# Automatic_Battery_Charger.net
KiCad netlist of a schematic drawn in EAGLE
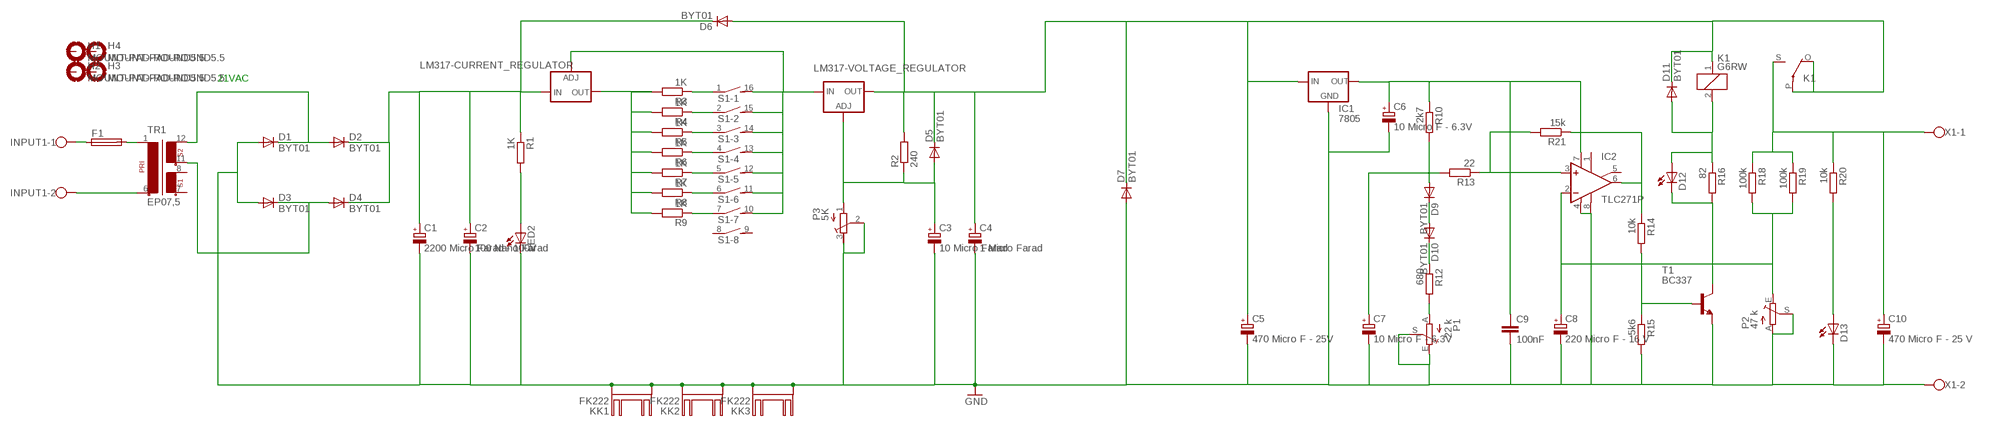
[diagram p0: schematic, sheet 1]

(export (version "E")
  (design (tool "Eeschema 10.0.6"))
  (components
    (comp (ref "C1")
      (value "2200 Micro Farad - 100V")
      (footprint "eagle-import:EB35D")
      (libsource (lib "eagle-import") (part "CPOL-EUE10-35"))
    )
    (comp (ref "C2")
      (value "100 Nano Farad")
      (footprint "eagle-import:E1,8-4")
      (libsource (lib "eagle-import") (part "CPOL-EUE1.8-4"))
    )
    (comp (ref "C3")
      (value "10 Micro Farad")
      (footprint "eagle-import:E2-5")
      (libsource (lib "eagle-import") (part "CPOL-EUE2-5"))
    )
    (comp (ref "C4")
      (value "1 Micro Farad")
      (footprint "eagle-import:E2-5")
      (libsource (lib "eagle-import") (part "CPOL-EUE2-5"))
    )
    (comp (ref "C5")
      (value "470 Micro F - 25V")
      (footprint "eagle-import:E3,5-10")
      (libsource (lib "eagle-import") (part "CPOL-EUE3.5-10"))
    )
    (comp (ref "C6")
      (value "10 Micro F - 6.3V")
      (footprint "eagle-import:E2-5")
      (libsource (lib "eagle-import") (part "CPOL-EUE2-5"))
    )
    (comp (ref "C7")
      (value "10 Micro F - 6.3V")
      (footprint "eagle-import:E2-5")
      (libsource (lib "eagle-import") (part "CPOL-EUE2-5"))
    )
    (comp (ref "C8")
      (value "220 Micro F - 16 V")
      (footprint "eagle-import:E2,5-7")
      (libsource (lib "eagle-import") (part "CPOL-EUE2.5-7"))
    )
    (comp (ref "C9")
      (value "100nF")
      (footprint "eagle-import:C025-030X050")
      (libsource (lib "eagle-import") (part "C-EU025-030X050"))
    )
    (comp (ref "C10")
      (value "470 Micro F - 25 V")
      (footprint "eagle-import:E3,5-10")
      (libsource (lib "eagle-import") (part "CPOL-EUE3.5-10"))
    )
    (comp (ref "D1")
      (value "BYT01")
      (footprint "eagle-import:F126-10")
      (libsource (lib "eagle-import") (part "BYT01"))
    )
    (comp (ref "D2")
      (value "BYT01")
      (footprint "eagle-import:F126-10")
      (libsource (lib "eagle-import") (part "BYT01"))
    )
    (comp (ref "D3")
      (value "BYT01")
      (footprint "eagle-import:F126-10")
      (libsource (lib "eagle-import") (part "BYT01"))
    )
    (comp (ref "D4")
      (value "BYT01")
      (footprint "eagle-import:F126-10")
      (libsource (lib "eagle-import") (part "BYT01"))
    )
    (comp (ref "D5")
      (value "BYT01")
      (footprint "eagle-import:F126-10")
      (libsource (lib "eagle-import") (part "BYT01"))
    )
    (comp (ref "D6")
      (value "BYT01")
      (footprint "eagle-import:F126-10")
      (libsource (lib "eagle-import") (part "BYT01"))
    )
    (comp (ref "D7")
      (value "BYT01")
      (footprint "eagle-import:F126-10")
      (libsource (lib "eagle-import") (part "BYT01"))
    )
    (comp (ref "D9")
      (value "BYT01")
      (footprint "eagle-import:F126-10")
      (libsource (lib "eagle-import") (part "BYT01"))
    )
    (comp (ref "D10")
      (value "BYT01")
      (footprint "eagle-import:F126-10")
      (libsource (lib "eagle-import") (part "BYT01"))
    )
    (comp (ref "D11")
      (value "BYT01")
      (footprint "eagle-import:F126-10")
      (libsource (lib "eagle-import") (part "BYT01"))
    )
    (comp (ref "D12")
      (value "LED5MM")
      (footprint "eagle-import:LED5MM")
      (libsource (lib "eagle-import") (part "LED5MM"))
    )
    (comp (ref "D13")
      (value "LED5MM")
      (footprint "eagle-import:LED5MM")
      (libsource (lib "eagle-import") (part "LED5MM"))
    )
    (comp (ref "F1")
      (value "SH22,5A")
      (footprint "eagle-import:SH22,5A")
      (fields (field (name "MPN") "0031.7701.11"))
      (libsource (lib "eagle-import") (part "SH22,5A"))
    )
    (comp (ref "H1")
      (value "MOUNT-PAD-ROUND5.5")
      (footprint "eagle-import:5,5-PAD")
      (libsource (lib "eagle-import") (part "MOUNT-PAD-ROUND5.5"))
    )
    (comp (ref "H2")
      (value "MOUNT-PAD-ROUND5.5")
      (footprint "eagle-import:5,5-PAD")
      (libsource (lib "eagle-import") (part "MOUNT-PAD-ROUND5.5"))
    )
    (comp (ref "H3")
      (value "MOUNT-PAD-ROUND5.5")
      (footprint "eagle-import:5,5-PAD")
      (libsource (lib "eagle-import") (part "MOUNT-PAD-ROUND5.5"))
    )
    (comp (ref "H4")
      (value "MOUNT-PAD-ROUND5.5")
      (footprint "eagle-import:5,5-PAD")
      (libsource (lib "eagle-import") (part "MOUNT-PAD-ROUND5.5"))
    )
    (comp (ref "IC1")
      (value "7805")
      (footprint "eagle-import:78XXS")
      (libsource (lib "eagle-import") (part "78XXS"))
    )
    (comp (ref "IC2")
      (value "TLC271P")
      (footprint "eagle-import:DIL08")
      (libsource (lib "eagle-import") (part "TLC271P"))
    )
    (comp (ref "INPUT1")
      (value "W237-102")
      (footprint "eagle-import:W237-102")
      (fields (field (name "MPN") "237-102"))
      (libsource (lib "eagle-import") (part "W237-102"))
    )
    (comp (ref "K1")
      (value "G6RW")
      (footprint "eagle-import:G6RW")
      (libsource (lib "eagle-import") (part "G6RW"))
    )
    (comp (ref "KK1")
      (value "FK222")
      (footprint "eagle-import:FK222")
      (libsource (lib "eagle-import") (part "FK222"))
    )
    (comp (ref "KK2")
      (value "FK222")
      (footprint "eagle-import:FK222")
      (libsource (lib "eagle-import") (part "FK222"))
    )
    (comp (ref "KK3")
      (value "FK222")
      (footprint "eagle-import:FK222")
      (libsource (lib "eagle-import") (part "FK222"))
    )
    (comp (ref "LED2")
      (value "LED5MM")
      (footprint "eagle-import:LED5MM")
      (libsource (lib "eagle-import") (part "LED5MM"))
    )
    (comp (ref "LM317-CURRENT_REGULATOR")
      (value "LM138-TS")
      (footprint "eagle-import:TO220S")
      (libsource (lib "eagle-import") (part "LM138-TS"))
    )
    (comp (ref "LM317-VOLTAGE_REGULATOR")
      (value "LM138-TS")
      (footprint "eagle-import:TO220S")
      (libsource (lib "eagle-import") (part "LM138-TS"))
    )
    (comp (ref "P1")
      (value "22 k")
      (footprint "eagle-import:LI10")
      (libsource (lib "eagle-import") (part "TRIM_EU-LI10"))
    )
    (comp (ref "P2")
      (value "47 k")
      (footprint "eagle-import:LI10")
      (libsource (lib "eagle-import") (part "TRIM_EU-LI10"))
    )
    (comp (ref "P3")
      (value "5K")
      (footprint "eagle-import:RTRIM64X")
      (libsource (lib "eagle-import") (part "R-TRIMM64X"))
    )
    (comp (ref "R1")
      (value "1K")
      (footprint "eagle-import:0207_7")
      (libsource (lib "eagle-import") (part "R-EU_0207/7"))
    )
    (comp (ref "R2")
      (value "240")
      (footprint "eagle-import:0207_7")
      (libsource (lib "eagle-import") (part "R-EU_0207/7"))
    )
    (comp (ref "R3")
      (value "1K")
      (footprint "eagle-import:0207_7")
      (libsource (lib "eagle-import") (part "R-EU_0207/7"))
    )
    (comp (ref "R4")
      (value "1K")
      (footprint "eagle-import:0207_7")
      (libsource (lib "eagle-import") (part "R-EU_0207/7"))
    )
    (comp (ref "R5")
      (value "1K")
      (footprint "eagle-import:0207_7")
      (libsource (lib "eagle-import") (part "R-EU_0207/7"))
    )
    (comp (ref "R6")
      (value "1K")
      (footprint "eagle-import:0207_10")
      (libsource (lib "eagle-import") (part "R-EU_0207/10"))
    )
    (comp (ref "R7")
      (value "1K")
      (footprint "eagle-import:0207_10")
      (libsource (lib "eagle-import") (part "R-EU_0207/10"))
    )
    (comp (ref "R8")
      (value "1K")
      (footprint "eagle-import:0207_15")
      (libsource (lib "eagle-import") (part "R-EU_0207/15"))
    )
    (comp (ref "R9")
      (value "1K")
      (footprint "eagle-import:0207_15")
      (libsource (lib "eagle-import") (part "R-EU_0207/15"))
    )
    (comp (ref "R10")
      (value "2k7")
      (footprint "eagle-import:0207_7")
      (libsource (lib "eagle-import") (part "R-EU_0207/7"))
    )
    (comp (ref "R12")
      (value "680")
      (footprint "eagle-import:0207_7")
      (libsource (lib "eagle-import") (part "R-EU_0207/7"))
    )
    (comp (ref "R13")
      (value "22")
      (footprint "eagle-import:0207_7")
      (libsource (lib "eagle-import") (part "R-EU_0207/7"))
    )
    (comp (ref "R14")
      (value "10k")
      (footprint "eagle-import:0207_7")
      (libsource (lib "eagle-import") (part "R-EU_0207/7"))
    )
    (comp (ref "R15")
      (value "5k6")
      (footprint "eagle-import:0207_7")
      (libsource (lib "eagle-import") (part "R-EU_0207/7"))
    )
    (comp (ref "R16")
      (value "82")
      (footprint "eagle-import:0207_7")
      (libsource (lib "eagle-import") (part "R-EU_0207/7"))
    )
    (comp (ref "R18")
      (value "100k")
      (footprint "eagle-import:0207_7")
      (libsource (lib "eagle-import") (part "R-EU_0207/7"))
    )
    (comp (ref "R19")
      (value "100k")
      (footprint "eagle-import:0207_7")
      (libsource (lib "eagle-import") (part "R-EU_0207/7"))
    )
    (comp (ref "R20")
      (value "10k")
      (footprint "eagle-import:0207_7")
      (libsource (lib "eagle-import") (part "R-EU_0207/7"))
    )
    (comp (ref "R21")
      (value "15k")
      (footprint "eagle-import:0207_7")
      (libsource (lib "eagle-import") (part "R-EU_0207/7"))
    )
    (comp (ref "S1")
      (value "DIP08SB")
      (footprint "eagle-import:DIP08SB")
      (libsource (lib "eagle-import") (part "DIP08SB"))
    )
    (comp (ref "T1")
      (value "BC337")
      (footprint "eagle-import:TO92")
      (libsource (lib "eagle-import") (part "BC337"))
    )
    (comp (ref "TR1")
      (value "EP07,5")
      (footprint "eagle-import:EP07,5")
      (libsource (lib "eagle-import") (part "EP07,5"))
    )
    (comp (ref "X1")
      (value "W237-102")
      (footprint "eagle-import:W237-102")
      (fields (field (name "MPN") "237-102"))
      (libsource (lib "eagle-import") (part "W237-102"))
    )
  )
  (nets
    (net (code "1") (name "GND") (class "Default")
      (node (ref "C1") (pin "-") (pinfunction "-_-") (pintype "passive"))
      (node (ref "C10") (pin "-") (pinfunction "-_-") (pintype "passive"))
      (node (ref "C2") (pin "-") (pinfunction "-_-") (pintype "passive"))
      (node (ref "C3") (pin "-") (pinfunction "-_-") (pintype "passive"))
      (node (ref "C4") (pin "-") (pinfunction "-_-") (pintype "passive"))
      (node (ref "C5") (pin "-") (pinfunction "-_-") (pintype "passive"))
      (node (ref "C6") (pin "-") (pinfunction "-_-") (pintype "passive"))
      (node (ref "C7") (pin "-") (pinfunction "-_-") (pintype "passive"))
      (node (ref "C8") (pin "-") (pinfunction "-_-") (pintype "passive"))
      (node (ref "C9") (pin "2") (pinfunction "2_2") (pintype "passive"))
      (node (ref "D1") (pin "A") (pinfunction "A_A") (pintype "passive"))
      (node (ref "D13") (pin "K") (pinfunction "C_K") (pintype "passive"))
      (node (ref "D3") (pin "A") (pinfunction "A_A") (pintype "passive"))
      (node (ref "D7") (pin "A") (pinfunction "A_A") (pintype "passive"))
      (node (ref "IC1") (pin "GND") (pinfunction "GND_GND") (pintype "input"))
      (node (ref "IC2") (pin "4") (pinfunction "V-_4") (pintype "power_in"))
      (node (ref "IC2") (pin "8") (pinfunction "OPT_8") (pintype "passive"))
      (node (ref "KK1") (pin "A2,8") (pinfunction "K_A2,8") (pintype "passive"))
      (node (ref "KK1") (pin "B2,8") (pinfunction "K_B2,8") (pintype "passive"))
      (node (ref "KK2") (pin "A2,8") (pinfunction "K_A2,8") (pintype "passive"))
      (node (ref "KK2") (pin "B2,8") (pinfunction "K_B2,8") (pintype "passive"))
      (node (ref "KK3") (pin "A2,8") (pinfunction "K_A2,8") (pintype "passive"))
      (node (ref "KK3") (pin "B2,8") (pinfunction "K_B2,8") (pintype "passive"))
      (node (ref "LED2") (pin "K") (pinfunction "C_K") (pintype "passive"))
      (node (ref "P1") (pin "E") (pinfunction "E_E") (pintype "passive"))
      (node (ref "P1") (pin "S") (pinfunction "S_S") (pintype "passive"))
      (node (ref "P2") (pin "A") (pinfunction "A_A") (pintype "passive"))
      (node (ref "P2") (pin "S") (pinfunction "S_S") (pintype "passive"))
      (node (ref "P3") (pin "2") (pinfunction "S_2") (pintype "passive"))
      (node (ref "P3") (pin "3") (pinfunction "A_3") (pintype "passive"))
      (node (ref "R15") (pin "2") (pinfunction "2_2") (pintype "passive"))
      (node (ref "T1") (pin "1") (pinfunction "E_1") (pintype "passive"))
      (node (ref "X1") (pin "2") (pinfunction "KL_2") (pintype "passive"))
    )
    (net (code "2") (name "Net-(C7-Pad+)") (class "Default")
      (node (ref "C7") (pin "+") (pinfunction "+_+") (pintype "passive"))
      (node (ref "D9") (pin "A") (pinfunction "A_A") (pintype "passive"))
      (node (ref "R10") (pin "2") (pinfunction "2_2") (pintype "passive"))
      (node (ref "R13") (pin "2") (pinfunction "2_2") (pintype "passive"))
    )
    (net (code "3") (name "Net-(D10-PadA)") (class "Default")
      (node (ref "D10") (pin "A") (pinfunction "A_A") (pintype "passive"))
      (node (ref "D9") (pin "C") (pinfunction "C_C") (pintype "passive"))
    )
    (net (code "4") (name "Net-(D10-PadC)") (class "Default")
      (node (ref "D10") (pin "C") (pinfunction "C_C") (pintype "passive"))
      (node (ref "R12") (pin "1") (pinfunction "1_1") (pintype "passive"))
    )
    (net (code "5") (name "Net-(D11-PadA)") (class "Default")
      (node (ref "D11") (pin "A") (pinfunction "A_A") (pintype "passive"))
      (node (ref "D12") (pin "A") (pinfunction "A_A") (pintype "passive"))
      (node (ref "K1") (pin "2") (pinfunction "2_2") (pintype "passive"))
      (node (ref "R16") (pin "1") (pinfunction "1_1") (pintype "passive"))
    )
    (net (code "6") (name "Net-(D12-C)") (class "Default")
      (node (ref "D12") (pin "K") (pinfunction "C_K") (pintype "passive"))
      (node (ref "R16") (pin "2") (pinfunction "2_2") (pintype "passive"))
      (node (ref "T1") (pin "3") (pinfunction "C_3") (pintype "passive"))
    )
    (net (code "7") (name "Net-(D13-PadA)") (class "Default")
      (node (ref "D13") (pin "A") (pinfunction "A_A") (pintype "passive"))
      (node (ref "R20") (pin "2") (pinfunction "2_2") (pintype "passive"))
    )
    (net (code "8") (name "Net-(F1-Pad2)") (class "Default")
      (node (ref "F1") (pin "2") (pinfunction "2_2") (pintype "passive"))
      (node (ref "TR1") (pin "1") (pinfunction "1_1") (pintype "passive"))
    )
    (net (code "9") (name "Net-(IC2-+IN)") (class "Default")
      (node (ref "IC2") (pin "3") (pinfunction "+IN_3") (pintype "input"))
      (node (ref "R13") (pin "1") (pinfunction "1_1") (pintype "passive"))
      (node (ref "R21") (pin "2") (pinfunction "2_2") (pintype "passive"))
    )
    (net (code "10") (name "Net-(IC2--IN)") (class "Default")
      (node (ref "C8") (pin "+") (pinfunction "+_+") (pintype "passive"))
      (node (ref "IC2") (pin "2") (pinfunction "-IN_2") (pintype "input"))
      (node (ref "P2") (pin "E") (pinfunction "E_E") (pintype "passive"))
      (node (ref "R18") (pin "2") (pinfunction "2_2") (pintype "passive"))
      (node (ref "R19") (pin "2") (pinfunction "2_2") (pintype "passive"))
    )
    (net (code "11") (name "Net-(IC2-OUT)") (class "Default")
      (node (ref "IC2") (pin "6") (pinfunction "OUT_6") (pintype "output"))
      (node (ref "R14") (pin "1") (pinfunction "1_1") (pintype "passive"))
      (node (ref "R21") (pin "1") (pinfunction "1_1") (pintype "passive"))
    )
    (net (code "12") (name "Net-(IC2-V+)") (class "Default")
      (node (ref "C6") (pin "+") (pinfunction "+_+") (pintype "passive"))
      (node (ref "C9") (pin "1") (pinfunction "1_1") (pintype "passive"))
      (node (ref "IC1") (pin "OUT") (pinfunction "OUT_OUT") (pintype "passive"))
      (node (ref "IC2") (pin "7") (pinfunction "V+_7") (pintype "power_in"))
      (node (ref "R10") (pin "1") (pinfunction "1_1") (pintype "passive"))
    )
    (net (code "13") (name "Net-(INPUT1A-KL)") (class "Default")
      (node (ref "F1") (pin "1") (pinfunction "1_1") (pintype "passive"))
      (node (ref "INPUT1") (pin "1") (pinfunction "KL_1") (pintype "passive"))
    )
    (net (code "14") (name "Net-(INPUT1B-KL)") (class "Default")
      (node (ref "INPUT1") (pin "2") (pinfunction "KL_2") (pintype "passive"))
      (node (ref "TR1") (pin "6") (pinfunction "2_6") (pintype "passive"))
    )
    (net (code "15") (name "Net-(LED2-PadA)") (class "Default")
      (node (ref "LED2") (pin "A") (pinfunction "A_A") (pintype "passive"))
      (node (ref "R1") (pin "2") (pinfunction "2_2") (pintype "passive"))
    )
    (net (code "16") (name "Net-(LM317-CURRENT_REGULATOR-ADJ)") (class "Default")
      (node (ref "LM317-CURRENT_REGULATOR") (pin "1") (pinfunction "ADJ_1") (pintype "input"))
      (node (ref "LM317-VOLTAGE_REGULATOR") (pin "3") (pinfunction "IN_3") (pintype "input"))
      (node (ref "S1") (pin "10") (pinfunction "2_10") (pintype "passive"))
      (node (ref "S1") (pin "11") (pinfunction "2_11") (pintype "passive"))
      (node (ref "S1") (pin "12") (pinfunction "2_12") (pintype "passive"))
      (node (ref "S1") (pin "13") (pinfunction "2_13") (pintype "passive"))
      (node (ref "S1") (pin "14") (pinfunction "2_14") (pintype "passive"))
      (node (ref "S1") (pin "15") (pinfunction "2_15") (pintype "passive"))
      (node (ref "S1") (pin "16") (pinfunction "2_16") (pintype "passive"))
    )
    (net (code "17") (name "Net-(LM317-CURRENT_REGULATOR-IN)") (class "Default")
      (node (ref "C1") (pin "+") (pinfunction "+_+") (pintype "passive"))
      (node (ref "C2") (pin "+") (pinfunction "+_+") (pintype "passive"))
      (node (ref "D2") (pin "C") (pinfunction "C_C") (pintype "passive"))
      (node (ref "D4") (pin "C") (pinfunction "C_C") (pintype "passive"))
      (node (ref "D6") (pin "C") (pinfunction "C_C") (pintype "passive"))
      (node (ref "LM317-CURRENT_REGULATOR") (pin "3") (pinfunction "IN_3") (pintype "input"))
      (node (ref "R1") (pin "1") (pinfunction "1_1") (pintype "passive"))
    )
    (net (code "18") (name "Net-(LM317-CURRENT_REGULATOR-OUT)") (class "Default")
      (node (ref "LM317-CURRENT_REGULATOR") (pin "2") (pinfunction "OUT_2") (pintype "passive"))
      (node (ref "R3") (pin "2") (pinfunction "2_2") (pintype "passive"))
      (node (ref "R4") (pin "2") (pinfunction "2_2") (pintype "passive"))
      (node (ref "R5") (pin "2") (pinfunction "2_2") (pintype "passive"))
      (node (ref "R6") (pin "2") (pinfunction "2_2") (pintype "passive"))
      (node (ref "R7") (pin "2") (pinfunction "2_2") (pintype "passive"))
      (node (ref "R8") (pin "2") (pinfunction "2_2") (pintype "passive"))
      (node (ref "R9") (pin "2") (pinfunction "2_2") (pintype "passive"))
    )
    (net (code "19") (name "Net-(LM317-VOLTAGE_REGULATOR-ADJ)") (class "Default")
      (node (ref "C3") (pin "+") (pinfunction "+_+") (pintype "passive"))
      (node (ref "D5") (pin "A") (pinfunction "A_A") (pintype "passive"))
      (node (ref "LM317-VOLTAGE_REGULATOR") (pin "1") (pinfunction "ADJ_1") (pintype "input"))
      (node (ref "P3") (pin "1") (pinfunction "E_1") (pintype "passive"))
      (node (ref "R2") (pin "1") (pinfunction "1_1") (pintype "passive"))
    )
    (net (code "20") (name "Net-(LM317-VOLTAGE_REGULATOR-OUT)") (class "Default")
      (node (ref "C4") (pin "+") (pinfunction "+_+") (pintype "passive"))
      (node (ref "C5") (pin "+") (pinfunction "+_+") (pintype "passive"))
      (node (ref "D11") (pin "C") (pinfunction "C_C") (pintype "passive"))
      (node (ref "D5") (pin "C") (pinfunction "C_C") (pintype "passive"))
      (node (ref "D6") (pin "A") (pinfunction "A_A") (pintype "passive"))
      (node (ref "D7") (pin "C") (pinfunction "C_C") (pintype "passive"))
      (node (ref "IC1") (pin "IN") (pinfunction "IN_IN") (pintype "input"))
      (node (ref "K1") (pin "1") (pinfunction "1_1") (pintype "passive"))
      (node (ref "K1") (pin "O") (pinfunction "O_O") (pintype "passive"))
      (node (ref "K1") (pin "P") (pinfunction "P_P") (pintype "passive"))
      (node (ref "LM317-VOLTAGE_REGULATOR") (pin "2") (pinfunction "OUT_2") (pintype "passive"))
      (node (ref "R2") (pin "2") (pinfunction "2_2") (pintype "passive"))
    )
    (net (code "21") (name "Net-(P1-PadA)") (class "Default")
      (node (ref "P1") (pin "A") (pinfunction "A_A") (pintype "passive"))
      (node (ref "R12") (pin "2") (pinfunction "2_2") (pintype "passive"))
    )
    (net (code "22") (name "Net-(R3-Pad1)") (class "Default")
      (node (ref "R3") (pin "1") (pinfunction "1_1") (pintype "passive"))
      (node (ref "S1") (pin "1") (pinfunction "1_1") (pintype "passive"))
    )
    (net (code "23") (name "Net-(S1B-1)") (class "Default")
      (node (ref "R4") (pin "1") (pinfunction "1_1") (pintype "passive"))
      (node (ref "S1") (pin "2") (pinfunction "1_2") (pintype "passive"))
    )
    (net (code "24") (name "Net-(S1C-1)") (class "Default")
      (node (ref "R5") (pin "1") (pinfunction "1_1") (pintype "passive"))
      (node (ref "S1") (pin "3") (pinfunction "1_3") (pintype "passive"))
    )
    (net (code "25") (name "Net-(S1D-1)") (class "Default")
      (node (ref "R6") (pin "1") (pinfunction "1_1") (pintype "passive"))
      (node (ref "S1") (pin "4") (pinfunction "1_4") (pintype "passive"))
    )
    (net (code "26") (name "Net-(S1E-1)") (class "Default")
      (node (ref "R7") (pin "1") (pinfunction "1_1") (pintype "passive"))
      (node (ref "S1") (pin "5") (pinfunction "1_5") (pintype "passive"))
    )
    (net (code "27") (name "Net-(S1F-1)") (class "Default")
      (node (ref "R8") (pin "1") (pinfunction "1_1") (pintype "passive"))
      (node (ref "S1") (pin "6") (pinfunction "1_6") (pintype "passive"))
    )
    (net (code "28") (name "Net-(S1G-1)") (class "Default")
      (node (ref "R9") (pin "1") (pinfunction "1_1") (pintype "passive"))
      (node (ref "S1") (pin "7") (pinfunction "1_7") (pintype "passive"))
    )
    (net (code "29") (name "Net-(T1-B)") (class "Default")
      (node (ref "R14") (pin "2") (pinfunction "2_2") (pintype "passive"))
      (node (ref "R15") (pin "1") (pinfunction "1_1") (pintype "passive"))
      (node (ref "T1") (pin "2") (pinfunction "B_2") (pintype "passive"))
    )
    (net (code "30") (name "Net-(TR1-5)") (class "Default")
      (node (ref "D3") (pin "C") (pinfunction "C_C") (pintype "passive"))
      (node (ref "D4") (pin "A") (pinfunction "A_A") (pintype "passive"))
      (node (ref "TR1") (pin "11") (pinfunction "5_11") (pintype "passive"))
    )
    (net (code "31") (name "Net-(TR1-6)") (class "Default")
      (node (ref "D1") (pin "C") (pinfunction "C_C") (pintype "passive"))
      (node (ref "D2") (pin "A") (pinfunction "A_A") (pintype "passive"))
      (node (ref "TR1") (pin "12") (pinfunction "6_12") (pintype "passive"))
    )
    (net (code "32") (name "Net-(X1A-KL)") (class "Default")
      (node (ref "C10") (pin "+") (pinfunction "+_+") (pintype "passive"))
      (node (ref "K1") (pin "S") (pinfunction "S_S") (pintype "passive"))
      (node (ref "R18") (pin "1") (pinfunction "1_1") (pintype "passive"))
      (node (ref "R19") (pin "1") (pinfunction "1_1") (pintype "passive"))
      (node (ref "R20") (pin "1") (pinfunction "1_1") (pintype "passive"))
      (node (ref "X1") (pin "1") (pinfunction "KL_1") (pintype "passive"))
    )
    (net (code "33") (name "unconnected-(H1-MOUNT-PadB5,5)") (class "Default")
      (node (ref "H1") (pin "B5,5") (pinfunction "MOUNT_B5,5") (pintype "passive"))
    )
    (net (code "34") (name "unconnected-(H2-MOUNT-PadB5,5)") (class "Default")
      (node (ref "H2") (pin "B5,5") (pinfunction "MOUNT_B5,5") (pintype "passive"))
    )
    (net (code "35") (name "unconnected-(H3-MOUNT-PadB5,5)") (class "Default")
      (node (ref "H3") (pin "B5,5") (pinfunction "MOUNT_B5,5") (pintype "passive"))
    )
    (net (code "36") (name "unconnected-(H4-MOUNT-PadB5,5)") (class "Default")
      (node (ref "H4") (pin "B5,5") (pinfunction "MOUNT_B5,5") (pintype "passive"))
    )
    (net (code "37") (name "unconnected-(IC2-ON1-Pad1)") (class "Default")
      (node (ref "IC2") (pin "1") (pinfunction "ON1_1") (pintype "passive"))
    )
    (net (code "38") (name "unconnected-(IC2-ON2-Pad5)") (class "Default")
      (node (ref "IC2") (pin "5") (pinfunction "ON2_5") (pintype "passive"))
    )
    (net (code "39") (name "unconnected-(S1H-1-Pad8)") (class "Default")
      (node (ref "S1") (pin "8") (pinfunction "1_8") (pintype "passive"))
    )
    (net (code "40") (name "unconnected-(S1H-2-Pad9)") (class "Default")
      (node (ref "S1") (pin "9") (pinfunction "2_9") (pintype "passive"))
    )
    (net (code "41") (name "unconnected-(TR1-3-Pad7)") (class "Default")
      (node (ref "TR1") (pin "7") (pinfunction "3_7") (pintype "passive"))
    )
    (net (code "42") (name "unconnected-(TR1-4-Pad8)") (class "Default")
      (node (ref "TR1") (pin "8") (pinfunction "4_8") (pintype "passive"))
    )
  )
)
